# RSD_M1_MOTORCYCLE_UNIT_V2.net
KiCad netlist of a schematic drawn in Altium Designer
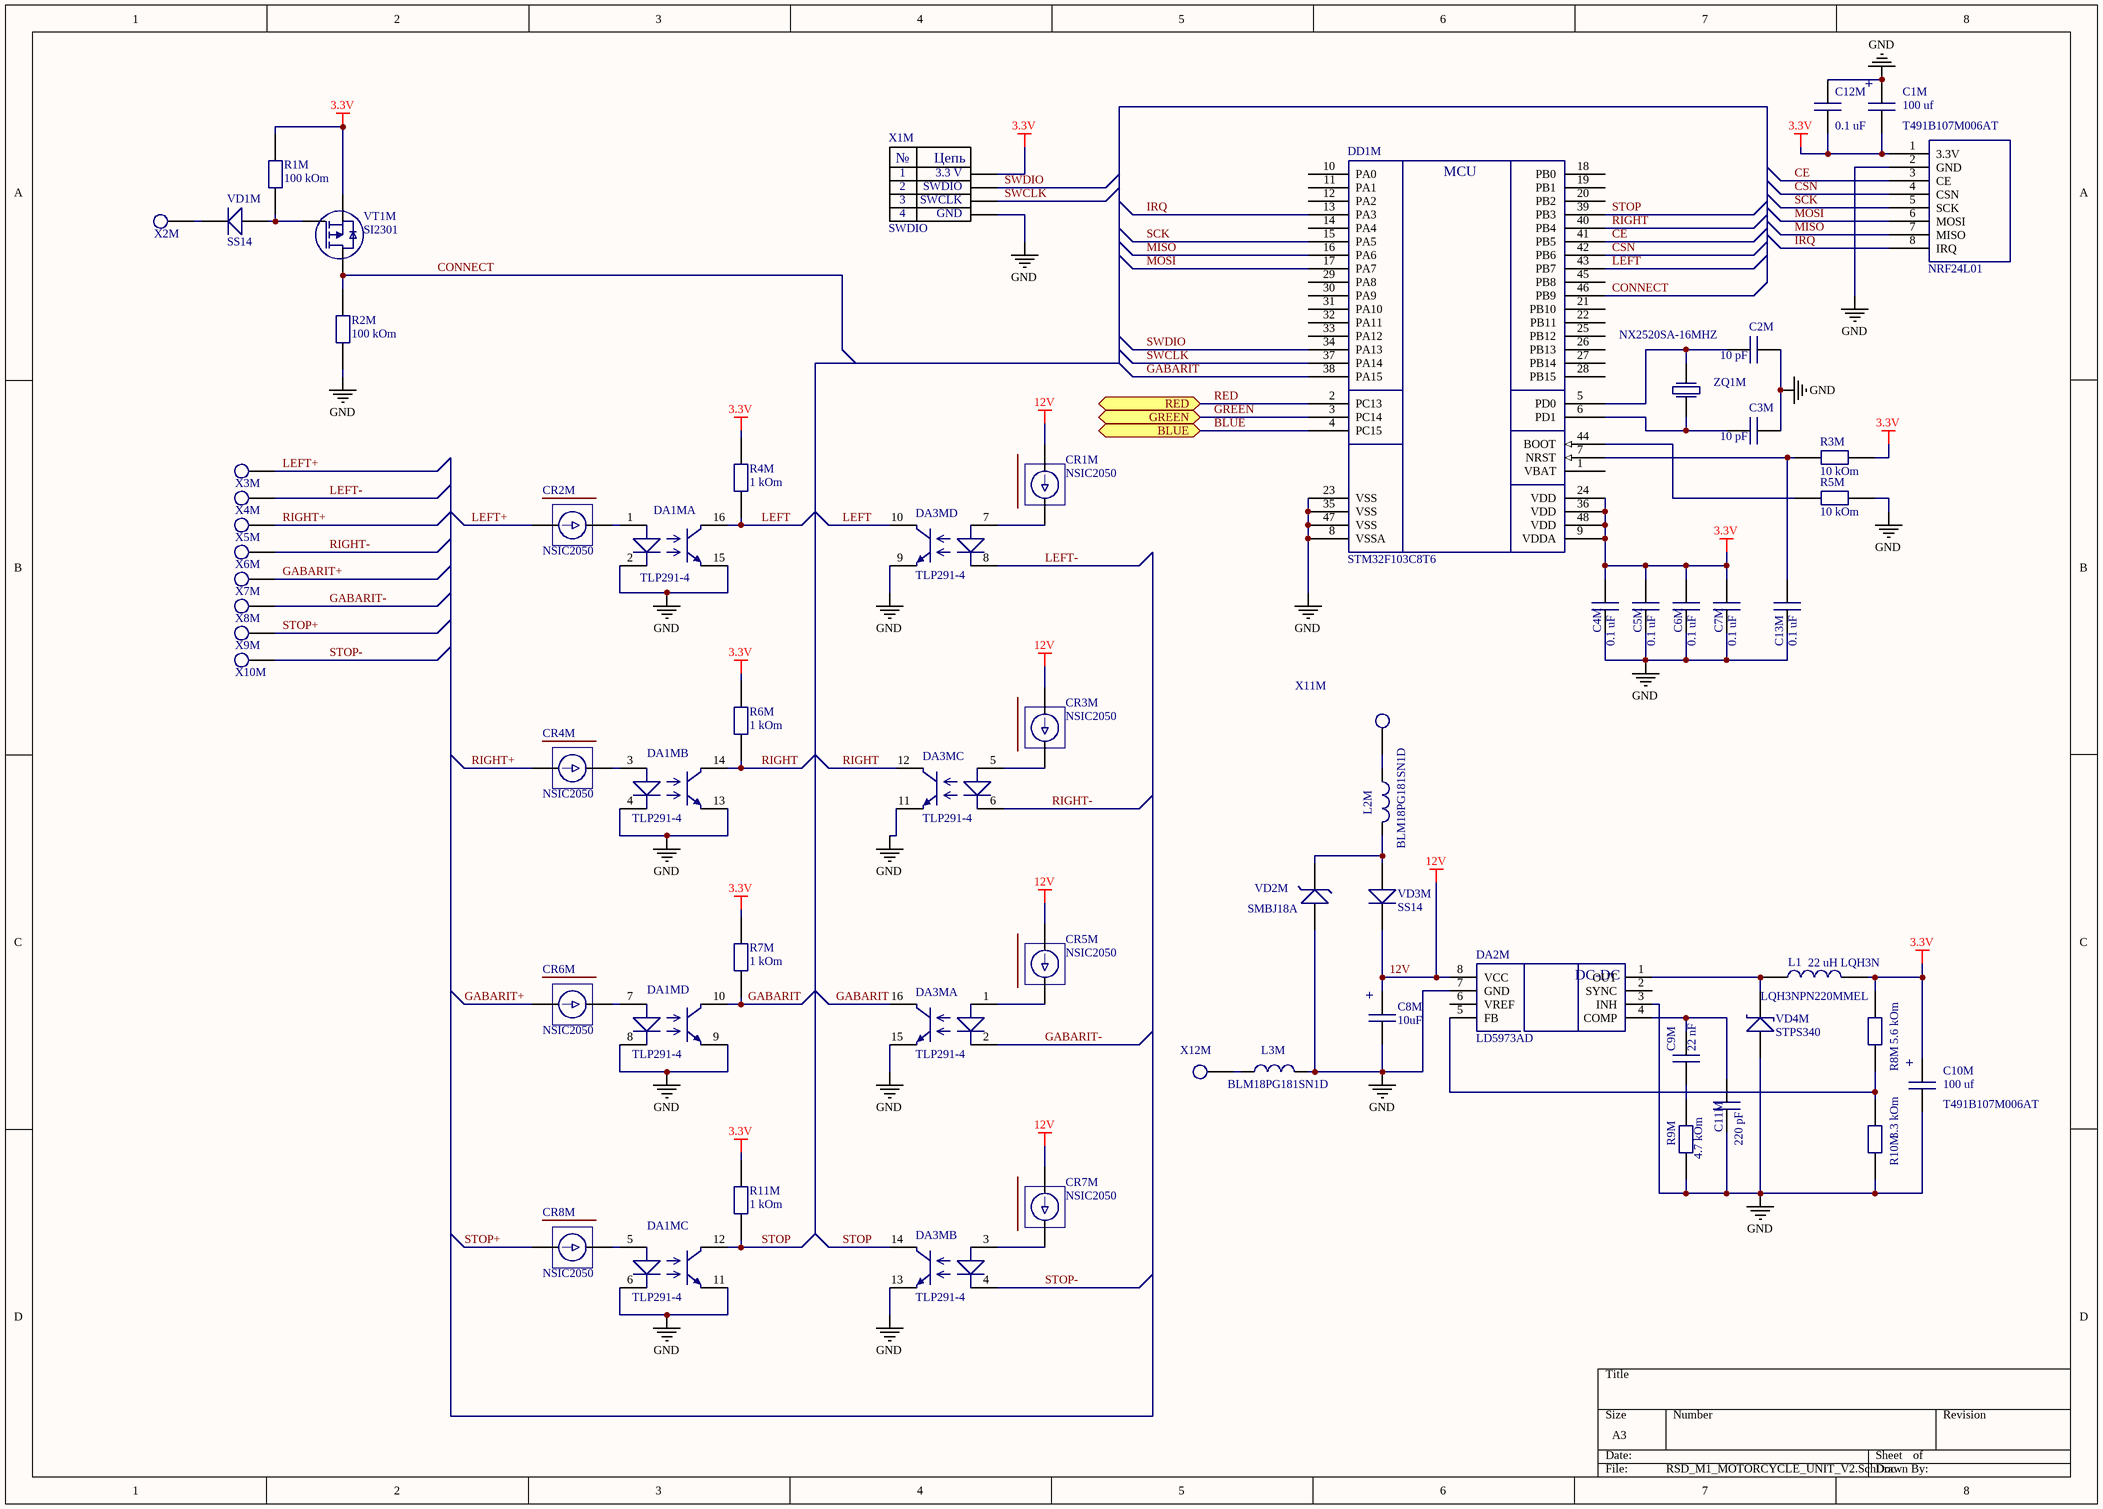
[diagram p0: RSD_M1_MOTORCYCLE_UNIT_V2.SchDoc]

(export (version "E")
  (design (tool "Eeschema 10.0.6"))
  (components
    (comp (ref "C1M")
      (value "100 uf")
      (footprint "tantal_case_B")
      (fields (field (name "ALTIUM_VALUE") "T491B107M006AT"))
      (libsource (lib "my_library") (part "Capacitor_Polar"))
    )
    (comp (ref "C2M")
      (value "10 pF")
      (footprint "CAP0603")
      (fields (field (name "Comment") "Capacitor"))
      (libsource (lib "my_library") (part "Capacitor"))
    )
    (comp (ref "C3M")
      (value "10 pF")
      (footprint "CAP0603")
      (fields (field (name "Comment") "Capacitor"))
      (libsource (lib "my_library") (part "Capacitor"))
    )
    (comp (ref "C4M")
      (value "0.1 uF")
      (footprint "CAP0603")
      (fields (field (name "Comment") "Capacitor"))
      (libsource (lib "my_library") (part "Capacitor"))
    )
    (comp (ref "C5M")
      (value "0.1 uF")
      (footprint "CAP0603")
      (fields (field (name "Comment") "Capacitor"))
      (libsource (lib "my_library") (part "Capacitor"))
    )
    (comp (ref "C6M")
      (value "0.1 uF")
      (footprint "CAP0603")
      (fields (field (name "Comment") "Capacitor"))
      (libsource (lib "my_library") (part "Capacitor"))
    )
    (comp (ref "C7M")
      (value "0.1 uF")
      (footprint "CAP0603")
      (fields (field (name "Comment") "Capacitor"))
      (libsource (lib "my_library") (part "Capacitor"))
    )
    (comp (ref "C8M")
      (value "10uF")
      (footprint "tantal_case_A")
      (fields (field (name "Comment") "Capacitor_Polar"))
      (libsource (lib "my_library") (part "Capacitor_Polar"))
    )
    (comp (ref "C9M")
      (value "22 nF")
      (footprint "CAP0603")
      (fields (field (name "Comment") "Capacitor"))
      (libsource (lib "my_library") (part "Capacitor"))
    )
    (comp (ref "C10M")
      (value "100 uf")
      (footprint "tantal_case_B")
      (fields (field (name "ALTIUM_VALUE") "T491B107M006AT"))
      (libsource (lib "my_library") (part "Capacitor_Polar"))
    )
    (comp (ref "C11M")
      (value "220 pF")
      (footprint "CAP0603")
      (fields (field (name "Comment") "Capacitor"))
      (libsource (lib "my_library") (part "Capacitor"))
    )
    (comp (ref "C12M")
      (value "0.1 uF")
      (footprint "CAP0603")
      (fields (field (name "Comment") "Capacitor"))
      (libsource (lib "my_library") (part "Capacitor"))
    )
    (comp (ref "C13M")
      (value "0.1 uF")
      (footprint "CAP0603")
      (fields (field (name "Comment") "Capacitor"))
      (libsource (lib "my_library") (part "Capacitor"))
    )
    (comp (ref "CR1M")
      (value "NSIC2050")
      (footprint "SMB1")
      (fields (field (name "Comment") "NSIC20XX"))
      (libsource (lib "") (part "NSIC20XX_1"))
    )
    (comp (ref "CR2M")
      (value "NSIC2050")
      (footprint "SMB1")
      (fields (field (name "Comment") "NSIC20XX"))
      (libsource (lib "my_library") (part "NSIC20XX"))
    )
    (comp (ref "CR3M")
      (value "NSIC2050")
      (footprint "SMB1")
      (fields (field (name "Comment") "NSIC20XX"))
      (libsource (lib "") (part "NSIC20XX_1"))
    )
    (comp (ref "CR4M")
      (value "NSIC2050")
      (footprint "SMB1")
      (fields (field (name "Comment") "NSIC20XX"))
      (libsource (lib "my_library") (part "NSIC20XX"))
    )
    (comp (ref "CR5M")
      (value "NSIC2050")
      (footprint "SMB1")
      (fields (field (name "Comment") "NSIC20XX"))
      (libsource (lib "") (part "NSIC20XX_1"))
    )
    (comp (ref "CR6M")
      (value "NSIC2050")
      (footprint "SMB1")
      (fields (field (name "Comment") "NSIC20XX"))
      (libsource (lib "my_library") (part "NSIC20XX"))
    )
    (comp (ref "CR7M")
      (value "NSIC2050")
      (footprint "SMB1")
      (fields (field (name "Comment") "NSIC20XX"))
      (libsource (lib "") (part "NSIC20XX_1"))
    )
    (comp (ref "CR8M")
      (value "NSIC2050")
      (footprint "SMB1")
      (fields (field (name "Comment") "NSIC20XX"))
      (libsource (lib "my_library") (part "NSIC20XX"))
    )
    (comp (ref "DA1M")
      (value "TLP291-4")
      (footprint "SOP16")
      (libsource (lib "my_library") (part "TLP291-4"))
    )
    (comp (ref "DA2M")
      (value "LD5973AD")
      (footprint "SOIC-8")
      (libsource (lib "my_library") (part "LD5973AD"))
    )
    (comp (ref "DA3M") (value "TLP291-4") (footprint "SOP16") (libsource (lib "") (part "TLP291-4_1")))
    (comp (ref "DD1M")
      (value "STM32F103C8T6")
      (footprint "STM32F103C8T6")
      (fields (field (name "Comment") "STM32F103C8Tx"))
      (libsource (lib "my_library") (part "STM32F103C8Tx"))
    )
    (comp (ref "L1")
      (value "22 uH LQH3N")
      (footprint "LQH3N")
      (fields (field (name "PN") "LQH3NPN220MMEL") (field (name "Comment") "coil"))
      (libsource (lib "") (part "coil_2"))
    )
    (comp (ref "L2M")
      (value "BLM18PG181SN1D")
      (footprint "IND0603")
      (fields (field (name "Comment") "coil"))
      (libsource (lib "") (part "coil_1"))
    )
    (comp (ref "L3M")
      (value "BLM18PG181SN1D")
      (footprint "IND0603")
      (fields (field (name "Comment") "coil"))
      (libsource (lib "my_library") (part "coil"))
    )
    (comp (ref "NRF1M")
      (value "NRF24L01")
      (footprint "NRF24L01")
      (libsource (lib "my_library") (part "NRF24L01"))
    )
    (comp (ref "R1M")
      (value "100 kOm")
      (footprint "Res0603")
      (fields (field (name "Comment") "Resistor"))
      (libsource (lib "my_library") (part "Resistor"))
    )
    (comp (ref "R2M")
      (value "100 kOm")
      (footprint "Res0603")
      (fields (field (name "Comment") "Resistor"))
      (libsource (lib "my_library") (part "Resistor"))
    )
    (comp (ref "R3M")
      (value "10 kOm")
      (footprint "Res0603")
      (fields (field (name "Comment") "Resistor"))
      (libsource (lib "my_library") (part "Resistor"))
    )
    (comp (ref "R4M")
      (value "1 kOm")
      (footprint "Res0603")
      (fields (field (name "Comment") "Resistor"))
      (libsource (lib "my_library") (part "Resistor"))
    )
    (comp (ref "R5M")
      (value "10 kOm")
      (footprint "Res0603")
      (fields (field (name "Comment") "Resistor"))
      (libsource (lib "my_library") (part "Resistor"))
    )
    (comp (ref "R6M")
      (value "1 kOm")
      (footprint "Res0603")
      (fields (field (name "Comment") "Resistor"))
      (libsource (lib "my_library") (part "Resistor"))
    )
    (comp (ref "R7M")
      (value "1 kOm")
      (footprint "Res0603")
      (fields (field (name "Comment") "Resistor"))
      (libsource (lib "my_library") (part "Resistor"))
    )
    (comp (ref "R8M")
      (value "5.6 kOm")
      (footprint "Res0603")
      (fields (field (name "Comment") "Resistor"))
      (libsource (lib "my_library") (part "Resistor"))
    )
    (comp (ref "R9M")
      (value "4.7 kOm")
      (footprint "Res0603")
      (fields (field (name "Comment") "Resistor"))
      (libsource (lib "my_library") (part "Resistor"))
    )
    (comp (ref "R10M")
      (value "3.3 kOm")
      (footprint "Res0603")
      (fields (field (name "Comment") "Resistor"))
      (libsource (lib "my_library") (part "Resistor"))
    )
    (comp (ref "R11M")
      (value "1 kOm")
      (footprint "Res0603")
      (fields (field (name "Comment") "Resistor"))
      (libsource (lib "my_library") (part "Resistor"))
    )
    (comp (ref "VD1M")
      (value "SS14")
      (footprint "SMA-F")
      (fields (field (name "Comment") "Diode"))
      (libsource (lib "my_library") (part "Diode"))
    )
    (comp (ref "VD2M")
      (value "SMBJ18A")
      (footprint "SMB1")
      (fields (field (name "Comment") "Suppressor"))
      (libsource (lib "my_library") (part "Suppressor"))
    )
    (comp (ref "VD3M")
      (value "SS14")
      (footprint "SMA-F")
      (fields (field (name "Comment") "Diode"))
      (libsource (lib "my_library") (part "Diode"))
    )
    (comp (ref "VD4M")
      (value "STPS340")
      (footprint "SMB1")
      (fields (field (name "Comment") "Schottky"))
      (libsource (lib "my_library") (part "Schottky"))
    )
    (comp (ref "VT1M")
      (value "SI2301")
      (footprint "SOT 23")
      (fields (field (name "Comment") "MOSFET-P"))
      (libsource (lib "my_library") (part "MOSFET-P"))
    )
    (comp (ref "X1M")
      (value "SWDIO")
      (footprint "SWDIO")
      (fields
        (field (name "1") "3.3 V")
        (field (name "2") "SWDIO")
        (field (name "3") "SWCLK")
        (field (name "4") "GND")
      )
      (libsource (lib "my_library") (part "SWDIO"))
    )
    (comp (ref "X2M")
      (value "WIRE_CONNECT")
      (footprint "WIRE_CONNECT")
      (libsource (lib "my_library") (part "WIRE_CONNECT"))
    )
    (comp (ref "X3M")
      (value "WIRE_CONNECT")
      (footprint "WIRE_CONNECT")
      (libsource (lib "my_library") (part "WIRE_CONNECT"))
    )
    (comp (ref "X4M")
      (value "WIRE_CONNECT")
      (footprint "WIRE_CONNECT")
      (libsource (lib "my_library") (part "WIRE_CONNECT"))
    )
    (comp (ref "X5M")
      (value "WIRE_CONNECT")
      (footprint "WIRE_CONNECT")
      (libsource (lib "my_library") (part "WIRE_CONNECT"))
    )
    (comp (ref "X6M")
      (value "WIRE_CONNECT")
      (footprint "WIRE_CONNECT")
      (libsource (lib "my_library") (part "WIRE_CONNECT"))
    )
    (comp (ref "X7M")
      (value "WIRE_CONNECT")
      (footprint "WIRE_CONNECT")
      (libsource (lib "my_library") (part "WIRE_CONNECT"))
    )
    (comp (ref "X8M")
      (value "WIRE_CONNECT")
      (footprint "WIRE_CONNECT")
      (libsource (lib "my_library") (part "WIRE_CONNECT"))
    )
    (comp (ref "X9M")
      (value "WIRE_CONNECT")
      (footprint "WIRE_CONNECT")
      (libsource (lib "my_library") (part "WIRE_CONNECT"))
    )
    (comp (ref "X10M")
      (value "WIRE_CONNECT")
      (footprint "WIRE_CONNECT")
      (libsource (lib "my_library") (part "WIRE_CONNECT"))
    )
    (comp (ref "X11M")
      (value "WIRE_CONNECT")
      (footprint "WIRE_CONNECT")
      (libsource (lib "") (part "WIRE_CONNECT_1"))
    )
    (comp (ref "X12M")
      (value "WIRE_CONNECT")
      (footprint "WIRE_CONNECT")
      (libsource (lib "my_library") (part "WIRE_CONNECT"))
    )
    (comp (ref "ZQ1M")
      (value "NX2520SA-16MHZ")
      (footprint "crystal")
      (fields (field (name "Comment") "Qartz"))
      (libsource (lib "my_library") (part "Qartz"))
    )
  )
  (nets
    (net (code "1") (name "/BLUE") (class "Default")
      (node (ref "DD1M") (pin "4") (pinfunction "PC15_4") (pintype "passive"))
    )
    (net (code "2") (name "/CE") (class "Default")
      (node (ref "DD1M") (pin "41") (pinfunction "PB5_41") (pintype "passive"))
      (node (ref "NRF1M") (pin "3") (pinfunction "CE_3") (pintype "passive"))
    )
    (net (code "3") (name "/CONNECT") (class "Default")
      (node (ref "DD1M") (pin "46") (pinfunction "PB9_46") (pintype "passive"))
      (node (ref "R2M") (pin "1") (pinfunction "1_1") (pintype "passive"))
      (node (ref "VT1M") (pin "D") (pintype "passive"))
    )
    (net (code "4") (name "/CSN") (class "Default")
      (node (ref "DD1M") (pin "42") (pinfunction "PB6_42") (pintype "passive"))
      (node (ref "NRF1M") (pin "4") (pinfunction "CSN_4") (pintype "passive"))
    )
    (net (code "5") (name "/GABARIT") (class "Default")
      (node (ref "DA1M") (pin "10") (pinfunction "10_10") (pintype "passive"))
      (node (ref "DA3M") (pin "16") (pinfunction "16_16") (pintype "passive"))
      (node (ref "DD1M") (pin "38") (pinfunction "PA15_38") (pintype "passive"))
      (node (ref "R7M") (pin "1") (pinfunction "1_1") (pintype "passive"))
    )
    (net (code "6") (name "/GABARIT+") (class "Default")
      (node (ref "CR6M") (pin "A") (pinfunction "A_A") (pintype "passive"))
      (node (ref "X7M") (pin "1") (pinfunction "1_1") (pintype "passive"))
    )
    (net (code "7") (name "/GABARIT-") (class "Default")
      (node (ref "DA3M") (pin "2") (pinfunction "2_2") (pintype "passive"))
      (node (ref "X8M") (pin "1") (pinfunction "1_1") (pintype "passive"))
    )
    (net (code "8") (name "/GREEN") (class "Default")
      (node (ref "DD1M") (pin "3") (pinfunction "PC14_3") (pintype "passive"))
    )
    (net (code "9") (name "/IRQ") (class "Default")
      (node (ref "DD1M") (pin "13") (pinfunction "PA3_13") (pintype "passive"))
      (node (ref "NRF1M") (pin "8") (pinfunction "IRQ_8") (pintype "passive"))
    )
    (net (code "10") (name "/LEFT") (class "Default")
      (node (ref "DA1M") (pin "16") (pinfunction "16_16") (pintype "passive"))
      (node (ref "DA3M") (pin "10") (pinfunction "10_10") (pintype "passive"))
      (node (ref "DD1M") (pin "43") (pinfunction "PB7_43") (pintype "passive"))
      (node (ref "R4M") (pin "1") (pinfunction "1_1") (pintype "passive"))
    )
    (net (code "11") (name "/LEFT+") (class "Default")
      (node (ref "CR2M") (pin "A") (pinfunction "A_A") (pintype "passive"))
      (node (ref "X3M") (pin "1") (pinfunction "1_1") (pintype "passive"))
    )
    (net (code "12") (name "/LEFT-") (class "Default")
      (node (ref "DA3M") (pin "8") (pinfunction "8_8") (pintype "passive"))
      (node (ref "X4M") (pin "1") (pinfunction "1_1") (pintype "passive"))
    )
    (net (code "13") (name "/MISO") (class "Default")
      (node (ref "DD1M") (pin "16") (pinfunction "PA6_16") (pintype "passive"))
      (node (ref "NRF1M") (pin "7") (pinfunction "MISO_7") (pintype "passive"))
    )
    (net (code "14") (name "/MOSI") (class "Default")
      (node (ref "DD1M") (pin "17") (pinfunction "PA7_17") (pintype "passive"))
      (node (ref "NRF1M") (pin "6") (pinfunction "MOSI_6") (pintype "passive"))
    )
    (net (code "15") (name "/RED") (class "Default")
      (node (ref "DD1M") (pin "2") (pinfunction "PC13_2") (pintype "passive"))
    )
    (net (code "16") (name "/RIGHT") (class "Default")
      (node (ref "DA1M") (pin "14") (pinfunction "14_14") (pintype "passive"))
      (node (ref "DA3M") (pin "12") (pinfunction "12_12") (pintype "passive"))
      (node (ref "DD1M") (pin "40") (pinfunction "PB4_40") (pintype "passive"))
      (node (ref "R6M") (pin "1") (pinfunction "1_1") (pintype "passive"))
    )
    (net (code "17") (name "/RIGHT+") (class "Default")
      (node (ref "CR4M") (pin "A") (pinfunction "A_A") (pintype "passive"))
      (node (ref "X5M") (pin "1") (pinfunction "1_1") (pintype "passive"))
    )
    (net (code "18") (name "/RIGHT-") (class "Default")
      (node (ref "DA3M") (pin "6") (pinfunction "6_6") (pintype "passive"))
      (node (ref "X6M") (pin "1") (pinfunction "1_1") (pintype "passive"))
    )
    (net (code "19") (name "/SCK") (class "Default")
      (node (ref "DD1M") (pin "15") (pinfunction "PA5_15") (pintype "passive"))
      (node (ref "NRF1M") (pin "5") (pinfunction "SCK_5") (pintype "passive"))
    )
    (net (code "20") (name "/STOP") (class "Default")
      (node (ref "DA1M") (pin "12") (pinfunction "12_12") (pintype "passive"))
      (node (ref "DA3M") (pin "14") (pinfunction "14_14") (pintype "passive"))
      (node (ref "DD1M") (pin "39") (pinfunction "PB3_39") (pintype "passive"))
      (node (ref "R11M") (pin "1") (pinfunction "1_1") (pintype "passive"))
    )
    (net (code "21") (name "/STOP+") (class "Default")
      (node (ref "CR8M") (pin "A") (pinfunction "A_A") (pintype "passive"))
      (node (ref "X9M") (pin "1") (pinfunction "1_1") (pintype "passive"))
    )
    (net (code "22") (name "/STOP-") (class "Default")
      (node (ref "DA3M") (pin "4") (pinfunction "4_4") (pintype "passive"))
      (node (ref "X10M") (pin "1") (pinfunction "1_1") (pintype "passive"))
    )
    (net (code "23") (name "/SWCLK") (class "Default")
      (node (ref "DD1M") (pin "37") (pinfunction "PA14_37") (pintype "passive"))
      (node (ref "X1M") (pin "3") (pinfunction "3_3") (pintype "passive"))
    )
    (net (code "24") (name "/SWDIO") (class "Default")
      (node (ref "DD1M") (pin "34") (pinfunction "PA13_34") (pintype "passive"))
      (node (ref "X1M") (pin "2") (pinfunction "2_2") (pintype "passive"))
    )
    (net (code "25") (name "3.3V") (class "Default")
      (node (ref "C10M") (pin "1") (pinfunction "1_1") (pintype "passive"))
      (node (ref "C12M") (pin "1") (pinfunction "1_1") (pintype "passive"))
      (node (ref "C1M") (pin "2") (pinfunction "2_2") (pintype "passive"))
      (node (ref "C4M") (pin "2") (pinfunction "2_2") (pintype "passive"))
      (node (ref "C5M") (pin "2") (pinfunction "2_2") (pintype "passive"))
      (node (ref "C6M") (pin "2") (pinfunction "2_2") (pintype "passive"))
      (node (ref "C7M") (pin "2") (pinfunction "2_2") (pintype "passive"))
      (node (ref "DD1M") (pin "24") (pinfunction "VDD_24") (pintype "passive"))
      (node (ref "DD1M") (pin "36") (pinfunction "VDD_36") (pintype "passive"))
      (node (ref "DD1M") (pin "48") (pinfunction "VDD_48") (pintype "passive"))
      (node (ref "DD1M") (pin "9") (pinfunction "VDDA_9") (pintype "passive"))
      (node (ref "L1") (pin "2") (pinfunction "2_2") (pintype "passive"))
      (node (ref "NRF1M") (pin "1") (pinfunction "3.3V_1") (pintype "passive"))
      (node (ref "R11M") (pin "2") (pinfunction "2_2") (pintype "passive"))
      (node (ref "R1M") (pin "1") (pinfunction "1_1") (pintype "passive"))
      (node (ref "R3M") (pin "2") (pinfunction "2_2") (pintype "passive"))
      (node (ref "R4M") (pin "2") (pinfunction "2_2") (pintype "passive"))
      (node (ref "R6M") (pin "2") (pinfunction "2_2") (pintype "passive"))
      (node (ref "R7M") (pin "2") (pinfunction "2_2") (pintype "passive"))
      (node (ref "R8M") (pin "1") (pinfunction "1_1") (pintype "passive"))
      (node (ref "VT1M") (pin "S") (pintype "passive"))
      (node (ref "X1M") (pin "1") (pinfunction "1_1") (pintype "passive"))
    )
    (net (code "26") (name "12V") (class "Default")
      (node (ref "C8M") (pin "1") (pinfunction "1_1") (pintype "passive"))
      (node (ref "CR1M") (pin "A") (pinfunction "A_A") (pintype "passive"))
      (node (ref "CR3M") (pin "A") (pinfunction "A_A") (pintype "passive"))
      (node (ref "CR5M") (pin "A") (pinfunction "A_A") (pintype "passive"))
      (node (ref "CR7M") (pin "A") (pinfunction "A_A") (pintype "passive"))
      (node (ref "DA2M") (pin "8") (pinfunction "VCC_8") (pintype "passive"))
      (node (ref "VD3M") (pin "1") (pinfunction "1_1") (pintype "passive"))
    )
    (net (code "27") (name "GND") (class "Default")
      (node (ref "C10M") (pin "2") (pinfunction "2_2") (pintype "passive"))
      (node (ref "C11M") (pin "1") (pinfunction "1_1") (pintype "passive"))
      (node (ref "C12M") (pin "2") (pinfunction "2_2") (pintype "passive"))
      (node (ref "C13M") (pin "1") (pinfunction "1_1") (pintype "passive"))
      (node (ref "C1M") (pin "1") (pinfunction "1_1") (pintype "passive"))
      (node (ref "C2M") (pin "1") (pinfunction "1_1") (pintype "passive"))
      (node (ref "C3M") (pin "1") (pinfunction "1_1") (pintype "passive"))
      (node (ref "C4M") (pin "1") (pinfunction "1_1") (pintype "passive"))
      (node (ref "C5M") (pin "1") (pinfunction "1_1") (pintype "passive"))
      (node (ref "C6M") (pin "1") (pinfunction "1_1") (pintype "passive"))
      (node (ref "C7M") (pin "1") (pinfunction "1_1") (pintype "passive"))
      (node (ref "C8M") (pin "2") (pinfunction "2_2") (pintype "passive"))
      (node (ref "DA1M") (pin "11") (pinfunction "11_11") (pintype "passive"))
      (node (ref "DA1M") (pin "13") (pinfunction "13_13") (pintype "passive"))
      (node (ref "DA1M") (pin "15") (pinfunction "15_15") (pintype "passive"))
      (node (ref "DA1M") (pin "2") (pinfunction "2_2") (pintype "passive"))
      (node (ref "DA1M") (pin "4") (pinfunction "4_4") (pintype "passive"))
      (node (ref "DA1M") (pin "6") (pinfunction "6_6") (pintype "passive"))
      (node (ref "DA1M") (pin "8") (pinfunction "8_8") (pintype "passive"))
      (node (ref "DA1M") (pin "9") (pinfunction "9_9") (pintype "passive"))
      (node (ref "DA2M") (pin "3") (pinfunction "INH_3") (pintype "passive"))
      (node (ref "DA2M") (pin "7") (pinfunction "GND_7") (pintype "passive"))
      (node (ref "DA3M") (pin "11") (pinfunction "11_11") (pintype "passive"))
      (node (ref "DA3M") (pin "13") (pinfunction "13_13") (pintype "passive"))
      (node (ref "DA3M") (pin "15") (pinfunction "15_15") (pintype "passive"))
      (node (ref "DA3M") (pin "9") (pinfunction "9_9") (pintype "passive"))
      (node (ref "DD1M") (pin "23") (pinfunction "VSS_23") (pintype "passive"))
      (node (ref "DD1M") (pin "35") (pinfunction "VSS_35") (pintype "passive"))
      (node (ref "DD1M") (pin "47") (pinfunction "VSS_47") (pintype "passive"))
      (node (ref "DD1M") (pin "8") (pinfunction "VSSA_8") (pintype "passive"))
      (node (ref "L3M") (pin "2") (pinfunction "2_2") (pintype "passive"))
      (node (ref "NRF1M") (pin "2") (pinfunction "GND_2") (pintype "passive"))
      (node (ref "R10M") (pin "2") (pinfunction "2_2") (pintype "passive"))
      (node (ref "R2M") (pin "2") (pinfunction "2_2") (pintype "passive"))
      (node (ref "R5M") (pin "2") (pinfunction "2_2") (pintype "passive"))
      (node (ref "R9M") (pin "2") (pinfunction "2_2") (pintype "passive"))
      (node (ref "VD2M") (pin "2") (pinfunction "2_2") (pintype "passive"))
      (node (ref "VD4M") (pin "2") (pinfunction "2_2") (pintype "passive"))
      (node (ref "X1M") (pin "4") (pinfunction "4_4") (pintype "passive"))
    )
    (net (code "28") (name "Net-(C9M-Pad1)") (class "Default")
      (node (ref "C9M") (pin "1") (pinfunction "1_1") (pintype "passive"))
      (node (ref "R9M") (pin "1") (pinfunction "1_1") (pintype "passive"))
    )
    (net (code "29") (name "Net-(CR1M-PadK)") (class "Default")
      (node (ref "CR1M") (pin "K") (pinfunction "K_K") (pintype "passive"))
      (node (ref "DA3M") (pin "7") (pinfunction "7_7") (pintype "passive"))
    )
    (net (code "30") (name "Net-(CR2M-PadK)") (class "Default")
      (node (ref "CR2M") (pin "K") (pinfunction "K_K") (pintype "passive"))
      (node (ref "DA1M") (pin "1") (pinfunction "1_1") (pintype "passive"))
    )
    (net (code "31") (name "Net-(CR3M-PadK)") (class "Default")
      (node (ref "CR3M") (pin "K") (pinfunction "K_K") (pintype "passive"))
      (node (ref "DA3M") (pin "5") (pinfunction "5_5") (pintype "passive"))
    )
    (net (code "32") (name "Net-(CR4M-PadK)") (class "Default")
      (node (ref "CR4M") (pin "K") (pinfunction "K_K") (pintype "passive"))
      (node (ref "DA1M") (pin "3") (pinfunction "3_3") (pintype "passive"))
    )
    (net (code "33") (name "Net-(CR5M-PadK)") (class "Default")
      (node (ref "CR5M") (pin "K") (pinfunction "K_K") (pintype "passive"))
      (node (ref "DA3M") (pin "1") (pinfunction "1_1") (pintype "passive"))
    )
    (net (code "34") (name "Net-(CR6M-PadK)") (class "Default")
      (node (ref "CR6M") (pin "K") (pinfunction "K_K") (pintype "passive"))
      (node (ref "DA1M") (pin "7") (pinfunction "7_7") (pintype "passive"))
    )
    (net (code "35") (name "Net-(CR7M-PadK)") (class "Default")
      (node (ref "CR7M") (pin "K") (pinfunction "K_K") (pintype "passive"))
      (node (ref "DA3M") (pin "3") (pinfunction "3_3") (pintype "passive"))
    )
    (net (code "36") (name "Net-(CR8M-PadK)") (class "Default")
      (node (ref "CR8M") (pin "K") (pinfunction "K_K") (pintype "passive"))
      (node (ref "DA1M") (pin "5") (pinfunction "5_5") (pintype "passive"))
    )
    (net (code "37") (name "Net-(DA2M-COMP)") (class "Default")
      (node (ref "C11M") (pin "2") (pinfunction "2_2") (pintype "passive"))
      (node (ref "C9M") (pin "2") (pinfunction "2_2") (pintype "passive"))
      (node (ref "DA2M") (pin "4") (pinfunction "COMP_4") (pintype "passive"))
    )
    (net (code "38") (name "Net-(DA2M-FB)") (class "Default")
      (node (ref "DA2M") (pin "5") (pinfunction "FB_5") (pintype "passive"))
      (node (ref "R10M") (pin "1") (pinfunction "1_1") (pintype "passive"))
      (node (ref "R8M") (pin "2") (pinfunction "2_2") (pintype "passive"))
    )
    (net (code "39") (name "Net-(DA2M-OUT)") (class "Default")
      (node (ref "DA2M") (pin "1") (pinfunction "OUT_1") (pintype "passive"))
      (node (ref "L1") (pin "1") (pinfunction "1_1") (pintype "passive"))
      (node (ref "VD4M") (pin "1") (pinfunction "1_1") (pintype "passive"))
    )
    (net (code "40") (name "Net-(DD1M-BOOT)") (class "Default")
      (node (ref "DD1M") (pin "44") (pinfunction "BOOT_44") (pintype "input"))
      (node (ref "R5M") (pin "1") (pinfunction "1_1") (pintype "passive"))
    )
    (net (code "41") (name "Net-(DD1M-NRST)") (class "Default")
      (node (ref "C13M") (pin "2") (pinfunction "2_2") (pintype "passive"))
      (node (ref "DD1M") (pin "7") (pinfunction "NRST_7") (pintype "input"))
      (node (ref "R3M") (pin "1") (pinfunction "1_1") (pintype "passive"))
    )
    (net (code "42") (name "Net-(DD1M-PD0)") (class "Default")
      (node (ref "C2M") (pin "2") (pinfunction "2_2") (pintype "passive"))
      (node (ref "DD1M") (pin "5") (pinfunction "PD0_5") (pintype "passive"))
      (node (ref "ZQ1M") (pin "2") (pinfunction "2_2") (pintype "passive"))
    )
    (net (code "43") (name "Net-(DD1M-PD1)") (class "Default")
      (node (ref "C3M") (pin "2") (pinfunction "2_2") (pintype "passive"))
      (node (ref "DD1M") (pin "6") (pinfunction "PD1_6") (pintype "passive"))
      (node (ref "ZQ1M") (pin "1") (pinfunction "1_1") (pintype "passive"))
    )
    (net (code "44") (name "Net-(L2M-Pad1)") (class "Default")
      (node (ref "L2M") (pin "1") (pinfunction "1_1") (pintype "passive"))
      (node (ref "X11M") (pin "1") (pinfunction "1_1") (pintype "passive"))
    )
    (net (code "45") (name "Net-(L2M-Pad2)") (class "Default")
      (node (ref "L2M") (pin "2") (pinfunction "2_2") (pintype "passive"))
      (node (ref "VD2M") (pin "1") (pinfunction "1_1") (pintype "passive"))
      (node (ref "VD3M") (pin "2") (pinfunction "2_2") (pintype "passive"))
    )
    (net (code "46") (name "Net-(L3M-Pad1)") (class "Default")
      (node (ref "L3M") (pin "1") (pinfunction "1_1") (pintype "passive"))
      (node (ref "X12M") (pin "1") (pinfunction "1_1") (pintype "passive"))
    )
    (net (code "47") (name "Net-(R1M-Pad2)") (class "Default")
      (node (ref "R1M") (pin "2") (pinfunction "2_2") (pintype "passive"))
      (node (ref "VD1M") (pin "2") (pinfunction "2_2") (pintype "passive"))
      (node (ref "VT1M") (pin "G") (pintype "passive"))
    )
    (net (code "48") (name "Net-(VD1M-Pad1)") (class "Default")
      (node (ref "VD1M") (pin "1") (pinfunction "1_1") (pintype "passive"))
      (node (ref "X2M") (pin "1") (pinfunction "1_1") (pintype "passive"))
    )
    (net (code "49") (name "unconnected-(DA2M-SYNC-Pad2)") (class "Default")
      (node (ref "DA2M") (pin "2") (pinfunction "SYNC_2") (pintype "passive"))
    )
    (net (code "50") (name "unconnected-(DA2M-VREF-Pad6)") (class "Default")
      (node (ref "DA2M") (pin "6") (pinfunction "VREF_6") (pintype "passive"))
    )
    (net (code "51") (name "unconnected-(DD1M-PA0-Pad10)") (class "Default")
      (node (ref "DD1M") (pin "10") (pinfunction "PA0_10") (pintype "passive"))
    )
    (net (code "52") (name "unconnected-(DD1M-PA1-Pad11)") (class "Default")
      (node (ref "DD1M") (pin "11") (pinfunction "PA1_11") (pintype "passive"))
    )
    (net (code "53") (name "unconnected-(DD1M-PA2-Pad12)") (class "Default")
      (node (ref "DD1M") (pin "12") (pinfunction "PA2_12") (pintype "passive"))
    )
    (net (code "54") (name "unconnected-(DD1M-PA4-Pad14)") (class "Default")
      (node (ref "DD1M") (pin "14") (pinfunction "PA4_14") (pintype "passive"))
    )
    (net (code "55") (name "unconnected-(DD1M-PA8-Pad29)") (class "Default")
      (node (ref "DD1M") (pin "29") (pinfunction "PA8_29") (pintype "passive"))
    )
    (net (code "56") (name "unconnected-(DD1M-PA9-Pad30)") (class "Default")
      (node (ref "DD1M") (pin "30") (pinfunction "PA9_30") (pintype "passive"))
    )
    (net (code "57") (name "unconnected-(DD1M-PA10-Pad31)") (class "Default")
      (node (ref "DD1M") (pin "31") (pinfunction "PA10_31") (pintype "passive"))
    )
    (net (code "58") (name "unconnected-(DD1M-PA11-Pad32)") (class "Default")
      (node (ref "DD1M") (pin "32") (pinfunction "PA11_32") (pintype "passive"))
    )
    (net (code "59") (name "unconnected-(DD1M-PA12-Pad33)") (class "Default")
      (node (ref "DD1M") (pin "33") (pinfunction "PA12_33") (pintype "passive"))
    )
    (net (code "60") (name "unconnected-(DD1M-PB0-Pad18)") (class "Default")
      (node (ref "DD1M") (pin "18") (pinfunction "PB0_18") (pintype "passive"))
    )
    (net (code "61") (name "unconnected-(DD1M-PB1-Pad19)") (class "Default")
      (node (ref "DD1M") (pin "19") (pinfunction "PB1_19") (pintype "passive"))
    )
    (net (code "62") (name "unconnected-(DD1M-PB2-Pad20)") (class "Default")
      (node (ref "DD1M") (pin "20") (pinfunction "PB2_20") (pintype "passive"))
    )
    (net (code "63") (name "unconnected-(DD1M-PB8-Pad45)") (class "Default")
      (node (ref "DD1M") (pin "45") (pinfunction "PB8_45") (pintype "passive"))
    )
    (net (code "64") (name "unconnected-(DD1M-PB10-Pad21)") (class "Default")
      (node (ref "DD1M") (pin "21") (pinfunction "PB10_21") (pintype "passive"))
    )
    (net (code "65") (name "unconnected-(DD1M-PB11-Pad22)") (class "Default")
      (node (ref "DD1M") (pin "22") (pinfunction "PB11_22") (pintype "passive"))
    )
    (net (code "66") (name "unconnected-(DD1M-PB12-Pad25)") (class "Default")
      (node (ref "DD1M") (pin "25") (pinfunction "PB12_25") (pintype "passive"))
    )
    (net (code "67") (name "unconnected-(DD1M-PB13-Pad26)") (class "Default")
      (node (ref "DD1M") (pin "26") (pinfunction "PB13_26") (pintype "passive"))
    )
    (net (code "68") (name "unconnected-(DD1M-PB14-Pad27)") (class "Default")
      (node (ref "DD1M") (pin "27") (pinfunction "PB14_27") (pintype "passive"))
    )
    (net (code "69") (name "unconnected-(DD1M-PB15-Pad28)") (class "Default")
      (node (ref "DD1M") (pin "28") (pinfunction "PB15_28") (pintype "passive"))
    )
    (net (code "70") (name "unconnected-(DD1M-VBAT-Pad1)") (class "Default")
      (node (ref "DD1M") (pin "1") (pinfunction "VBAT_1") (pintype "passive"))
    )
  )
)
